# Motorboard.net
KiCad netlist of a schematic drawn in EAGLE
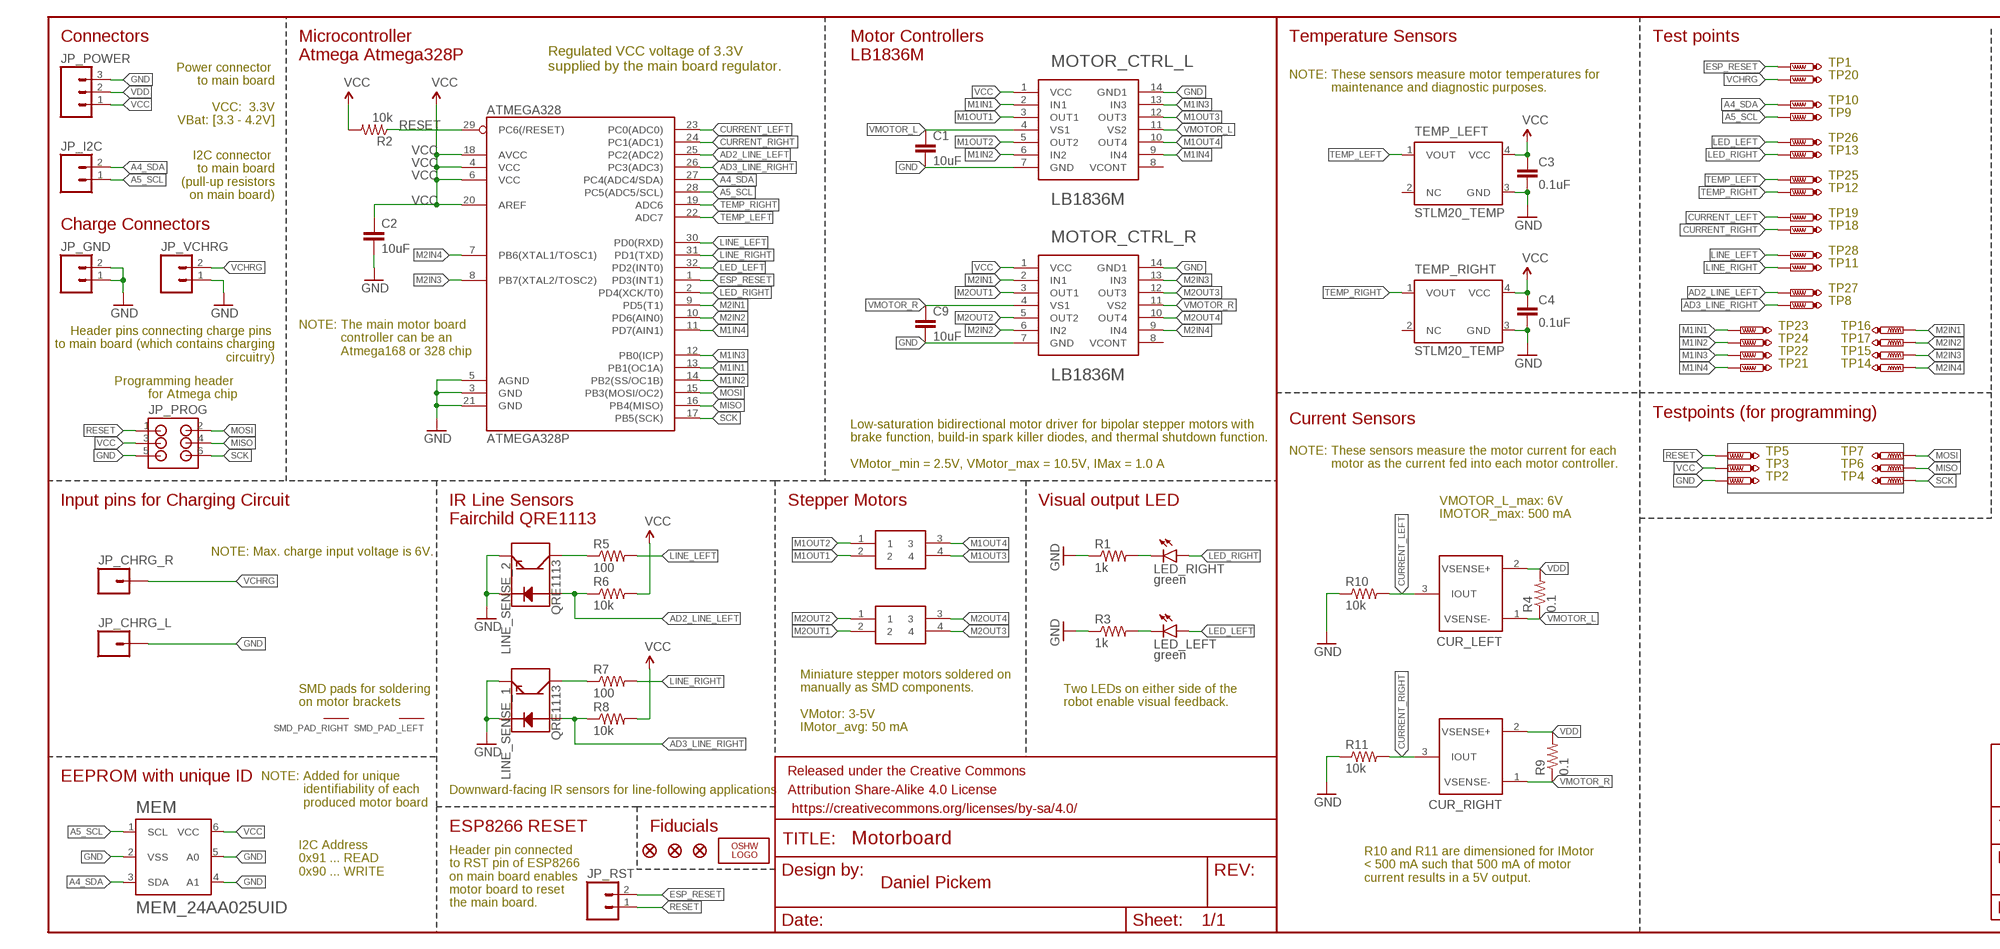
[diagram p0: schematic, sheet 1, part 1 of 2]
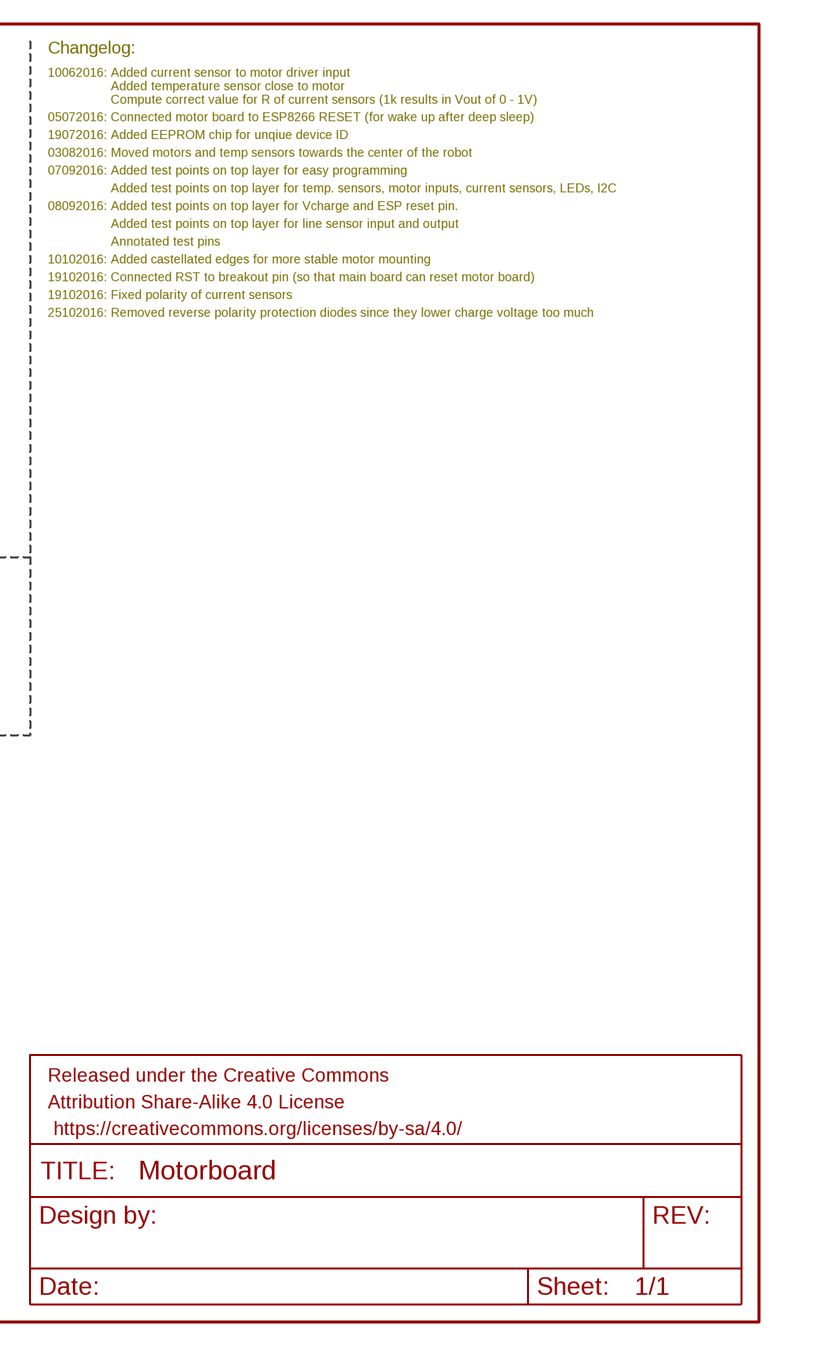
[diagram p1: schematic, sheet 1, part 2 of 2]

(export (version "E")
  (design (tool "Eeschema 10.0.6"))
  (components
    (comp (ref "ATMEGA328P")
      (value "ATMEGA328")
      (footprint "eagle-import:TQFP32-08")
      (libsource (lib "eagle-import") (part "ATMEGA168"))
    )
    (comp (ref "C1")
      (value "10uF")
      (footprint "eagle-import:0805")
      (libsource (lib "eagle-import") (part "2.2UF-25V-+80/-20(0805)"))
    )
    (comp (ref "C2")
      (value "10uF")
      (footprint "eagle-import:0805")
      (libsource (lib "eagle-import") (part "2.2UF-25V-+80/-20(0805)"))
    )
    (comp (ref "C3")
      (value "0.1uF")
      (footprint "eagle-import:0603-CAP")
      (libsource (lib "eagle-import") (part "4.7UF-6.3V-10%(0603)0603"))
    )
    (comp (ref "C4")
      (value "0.1uF")
      (footprint "eagle-import:0603-CAP")
      (libsource (lib "eagle-import") (part "4.7UF-6.3V-10%(0603)0603"))
    )
    (comp (ref "C9")
      (value "10uF")
      (footprint "eagle-import:0805")
      (libsource (lib "eagle-import") (part "2.2UF-25V-+80/-20(0805)"))
    )
    (comp (ref "CUR_LEFT")
      (value "ZXCT1009_CURRENT")
      (footprint "eagle-import:SOT23-3")
      (libsource (lib "eagle-import") (part "ZXCT1009_CURRENT"))
    )
    (comp (ref "CUR_RIGHT")
      (value "ZXCT1009_CURRENT")
      (footprint "eagle-import:SOT23-3")
      (libsource (lib "eagle-import") (part "ZXCT1009_CURRENT"))
    )
    (comp (ref "FRAME1")
      (value "FRAME-LETTER")
      (footprint "eagle-import:CREATIVE_COMMONS")
      (libsource (lib "eagle-import") (part "FRAME-LETTER"))
    )
    (comp (ref "FRAME2")
      (value "FRAME-LETTER")
      (footprint "eagle-import:CREATIVE_COMMONS")
      (libsource (lib "eagle-import") (part "FRAME-LETTER"))
    )
    (comp (ref "JP3")
      (value "FIDUCIAL1X2.5")
      (footprint "eagle-import:FIDUCIAL-1X2.5")
      (libsource (lib "eagle-import") (part "FIDUCIAL1X2.5"))
    )
    (comp (ref "JP4")
      (value "FIDUCIAL1X2.5")
      (footprint "eagle-import:FIDUCIAL-1X2.5")
      (libsource (lib "eagle-import") (part "FIDUCIAL1X2.5"))
    )
    (comp (ref "JP5")
      (value "FIDUCIAL1X2.5")
      (footprint "eagle-import:FIDUCIAL-1X2.5")
      (libsource (lib "eagle-import") (part "FIDUCIAL1X2.5"))
    )
    (comp (ref "JP_CHRG_L")
      (value "M01NOSILK-KIT")
      (footprint "eagle-import:1X01NS-KIT")
      (libsource (lib "eagle-import") (part "M01NOSILK-KIT"))
    )
    (comp (ref "JP_CHRG_R")
      (value "M01NOSILK-KIT")
      (footprint "eagle-import:1X01NS-KIT")
      (libsource (lib "eagle-import") (part "M01NOSILK-KIT"))
    )
    (comp (ref "JP_GND")
      (value "M021X02_NO_SILK")
      (footprint "eagle-import:1X02_NO_SILK")
      (libsource (lib "eagle-import") (part "M021X02_NO_SILK"))
    )
    (comp (ref "JP_I2C")
      (value "M02PTH")
      (footprint "eagle-import:1X02")
      (libsource (lib "eagle-import") (part "M02PTH"))
    )
    (comp (ref "JP_POWER")
      (value "supply")
      (footprint "eagle-import:1X03")
      (libsource (lib "eagle-import") (part "M03PTH"))
    )
    (comp (ref "JP_PROG")
      (value "3X2_SMD_HEADER")
      (footprint "eagle-import:3X2_SMD_HEADER")
      (libsource (lib "eagle-import") (part "3X2_SMD_HEADER"))
    )
    (comp (ref "JP_RST")
      (value "M021X02_NO_SILK")
      (footprint "eagle-import:1X02_NO_SILK")
      (libsource (lib "eagle-import") (part "M021X02_NO_SILK"))
    )
    (comp (ref "JP_VCHRG")
      (value "M021X02_NO_SILK")
      (footprint "eagle-import:1X02_NO_SILK")
      (libsource (lib "eagle-import") (part "M021X02_NO_SILK"))
    )
    (comp (ref "LED_LEFT")
      (value "green")
      (footprint "eagle-import:LED-0603")
      (libsource (lib "eagle-import") (part "LED0603"))
    )
    (comp (ref "LED_RIGHT")
      (value "green")
      (footprint "eagle-import:LED-0603")
      (libsource (lib "eagle-import") (part "LED0603"))
    )
    (comp (ref "LINE_SENSE_1")
      (value "QRE1113")
      (footprint "eagle-import:QRE1113")
      (libsource (lib "eagle-import") (part "QRE1113"))
    )
    (comp (ref "LINE_SENSE_2")
      (value "QRE1113")
      (footprint "eagle-import:QRE1113")
      (libsource (lib "eagle-import") (part "QRE1113"))
    )
    (comp (ref "LOGO1")
      (value "OSHW_LOGO_FILLX0100-NT")
      (footprint "eagle-import:OSHW_FILLX100_NOTEXT")
      (libsource (lib "eagle-import") (part "OSHW_LOGO_FILLX0100-NT"))
    )
    (comp (ref "M1")
      (value "STEPPER_MOTOR_SMD")
      (footprint "eagle-import:STEPPER_MOTOR_SMD")
      (libsource (lib "eagle-import") (part "STEPPER_MOTOR_SMD"))
    )
    (comp (ref "M2")
      (value "STEPPER_MOTOR_SMD")
      (footprint "eagle-import:STEPPER_MOTOR_SMD")
      (libsource (lib "eagle-import") (part "STEPPER_MOTOR_SMD"))
    )
    (comp (ref "MEM")
      (value "MEM_24AA025UID")
      (footprint "eagle-import:SOT23-6-MCP1640")
      (libsource (lib "eagle-import") (part "MEM_24AA025UID"))
    )
    (comp (ref "MOTOR_CTRL_L")
      (value "LB1836M")
      (footprint "eagle-import:LSOP-14")
      (libsource (lib "eagle-import") (part "LB1836M"))
    )
    (comp (ref "MOTOR_CTRL_R")
      (value "LB1836M")
      (footprint "eagle-import:LSOP-14")
      (libsource (lib "eagle-import") (part "LB1836M"))
    )
    (comp (ref "R1")
      (value "1k")
      (footprint "eagle-import:0603")
      (libsource (lib "eagle-import") (part "1.5KOHM1/10W1%(0603)"))
    )
    (comp (ref "R2")
      (value "10k")
      (footprint "eagle-import:0603")
      (libsource (lib "eagle-import") (part "1.5KOHM1/10W1%(0603)"))
    )
    (comp (ref "R3")
      (value "1k")
      (footprint "eagle-import:0603")
      (libsource (lib "eagle-import") (part "1.5KOHM1/10W1%(0603)"))
    )
    (comp (ref "R4")
      (value "0.1")
      (footprint "eagle-import:1206")
      (libsource (lib "eagle-import") (part "RESISTOR1206"))
    )
    (comp (ref "R5")
      (value "100")
      (footprint "eagle-import:0603")
      (libsource (lib "eagle-import") (part "1.5KOHM1/10W1%(0603)"))
    )
    (comp (ref "R6")
      (value "10k")
      (footprint "eagle-import:0603")
      (libsource (lib "eagle-import") (part "1.5KOHM1/10W1%(0603)"))
    )
    (comp (ref "R7")
      (value "100")
      (footprint "eagle-import:0603")
      (libsource (lib "eagle-import") (part "1.5KOHM1/10W1%(0603)"))
    )
    (comp (ref "R8")
      (value "10k")
      (footprint "eagle-import:0603")
      (libsource (lib "eagle-import") (part "1.5KOHM1/10W1%(0603)"))
    )
    (comp (ref "R9")
      (value "0.1")
      (footprint "eagle-import:1206")
      (libsource (lib "eagle-import") (part "RESISTOR1206"))
    )
    (comp (ref "R10")
      (value "10k")
      (footprint "eagle-import:0603")
      (libsource (lib "eagle-import") (part "1.5KOHM1/10W1%(0603)"))
    )
    (comp (ref "R11")
      (value "10k")
      (footprint "eagle-import:0603")
      (libsource (lib "eagle-import") (part "1.5KOHM1/10W1%(0603)"))
    )
    (comp (ref "SMD_PAD_LEFT")
      (value "PIN_SMD2.5X1.0")
      (footprint "eagle-import:PIN_SMD_2.5X1.0")
      (libsource (lib "eagle-import") (part "PIN_SMD2.5X1.0"))
    )
    (comp (ref "SMD_PAD_RIGHT")
      (value "PIN_SMD2.5X1.0")
      (footprint "eagle-import:PIN_SMD_2.5X1.0")
      (libsource (lib "eagle-import") (part "PIN_SMD2.5X1.0"))
    )
    (comp (ref "TEMP_LEFT")
      (value "STLM20_TEMP")
      (footprint "eagle-import:UDFN4")
      (libsource (lib "eagle-import") (part "STLM20_TEMP"))
    )
    (comp (ref "TEMP_RIGHT")
      (value "STLM20_TEMP")
      (footprint "eagle-import:UDFN4")
      (libsource (lib "eagle-import") (part "STLM20_TEMP"))
    )
    (comp (ref "TP1")
      (value "PTR1B1,27")
      (footprint "eagle-import:B1,27")
      (libsource (lib "eagle-import") (part "PTR1B1,27"))
    )
    (comp (ref "TP2")
      (value "PTR1B1,27")
      (footprint "eagle-import:B1,27")
      (libsource (lib "eagle-import") (part "PTR1B1,27"))
    )
    (comp (ref "TP3")
      (value "PTR1B1,27")
      (footprint "eagle-import:B1,27")
      (libsource (lib "eagle-import") (part "PTR1B1,27"))
    )
    (comp (ref "TP4")
      (value "PTR1B1,27")
      (footprint "eagle-import:B1,27")
      (libsource (lib "eagle-import") (part "PTR1B1,27"))
    )
    (comp (ref "TP5")
      (value "PTR1B1,27")
      (footprint "eagle-import:B1,27")
      (libsource (lib "eagle-import") (part "PTR1B1,27"))
    )
    (comp (ref "TP6")
      (value "PTR1B1,27")
      (footprint "eagle-import:B1,27")
      (libsource (lib "eagle-import") (part "PTR1B1,27"))
    )
    (comp (ref "TP7")
      (value "PTR1B1,27")
      (footprint "eagle-import:B1,27")
      (libsource (lib "eagle-import") (part "PTR1B1,27"))
    )
    (comp (ref "TP8")
      (value "PTR1B1,27")
      (footprint "eagle-import:B1,27")
      (libsource (lib "eagle-import") (part "PTR1B1,27"))
    )
    (comp (ref "TP9")
      (value "PTR1B1,27")
      (footprint "eagle-import:B1,27")
      (libsource (lib "eagle-import") (part "PTR1B1,27"))
    )
    (comp (ref "TP10")
      (value "PTR1B1,27")
      (footprint "eagle-import:B1,27")
      (libsource (lib "eagle-import") (part "PTR1B1,27"))
    )
    (comp (ref "TP11")
      (value "PTR1B1,27")
      (footprint "eagle-import:B1,27")
      (libsource (lib "eagle-import") (part "PTR1B1,27"))
    )
    (comp (ref "TP12")
      (value "PTR1B1,27")
      (footprint "eagle-import:B1,27")
      (libsource (lib "eagle-import") (part "PTR1B1,27"))
    )
    (comp (ref "TP13")
      (value "PTR1B1,27")
      (footprint "eagle-import:B1,27")
      (libsource (lib "eagle-import") (part "PTR1B1,27"))
    )
    (comp (ref "TP14")
      (value "PTR1B1,27")
      (footprint "eagle-import:B1,27")
      (libsource (lib "eagle-import") (part "PTR1B1,27"))
    )
    (comp (ref "TP15")
      (value "PTR1B1,27")
      (footprint "eagle-import:B1,27")
      (libsource (lib "eagle-import") (part "PTR1B1,27"))
    )
    (comp (ref "TP16")
      (value "PTR1B1,27")
      (footprint "eagle-import:B1,27")
      (libsource (lib "eagle-import") (part "PTR1B1,27"))
    )
    (comp (ref "TP17")
      (value "PTR1B1,27")
      (footprint "eagle-import:B1,27")
      (libsource (lib "eagle-import") (part "PTR1B1,27"))
    )
    (comp (ref "TP18")
      (value "PTR1B1,27")
      (footprint "eagle-import:B1,27")
      (libsource (lib "eagle-import") (part "PTR1B1,27"))
    )
    (comp (ref "TP19")
      (value "PTR1B1,27")
      (footprint "eagle-import:B1,27")
      (libsource (lib "eagle-import") (part "PTR1B1,27"))
    )
    (comp (ref "TP20")
      (value "PTR1B1,27")
      (footprint "eagle-import:B1,27")
      (libsource (lib "eagle-import") (part "PTR1B1,27"))
    )
    (comp (ref "TP21")
      (value "PTR1B1,27")
      (footprint "eagle-import:B1,27")
      (libsource (lib "eagle-import") (part "PTR1B1,27"))
    )
    (comp (ref "TP22")
      (value "PTR1B1,27")
      (footprint "eagle-import:B1,27")
      (libsource (lib "eagle-import") (part "PTR1B1,27"))
    )
    (comp (ref "TP23")
      (value "PTR1B1,27")
      (footprint "eagle-import:B1,27")
      (libsource (lib "eagle-import") (part "PTR1B1,27"))
    )
    (comp (ref "TP24")
      (value "PTR1B1,27")
      (footprint "eagle-import:B1,27")
      (libsource (lib "eagle-import") (part "PTR1B1,27"))
    )
    (comp (ref "TP25")
      (value "PTR1B1,27")
      (footprint "eagle-import:B1,27")
      (libsource (lib "eagle-import") (part "PTR1B1,27"))
    )
    (comp (ref "TP26")
      (value "PTR1B1,27")
      (footprint "eagle-import:B1,27")
      (libsource (lib "eagle-import") (part "PTR1B1,27"))
    )
    (comp (ref "TP27")
      (value "PTR1B1,27")
      (footprint "eagle-import:B1,27")
      (libsource (lib "eagle-import") (part "PTR1B1,27"))
    )
    (comp (ref "TP28")
      (value "PTR1B1,27")
      (footprint "eagle-import:B1,27")
      (libsource (lib "eagle-import") (part "PTR1B1,27"))
    )
  )
  (nets
    (net (code "1") (name "A4_SDA") (class "Default")
      (node (ref "ATMEGA328P") (pin "27") (pinfunction "PC4(ADC4/SDA)_27") (pintype "bidirectional"))
      (node (ref "JP_I2C") (pin "2") (pinfunction "2_2") (pintype "passive"))
      (node (ref "MEM") (pin "3") (pinfunction "SDA_3") (pintype "bidirectional"))
      (node (ref "TP10") (pin "TP") (pinfunction "TP_TP") (pintype "input"))
    )
    (net (code "2") (name "A5_SCL") (class "Default")
      (node (ref "ATMEGA328P") (pin "28") (pinfunction "PC5(ADC5/SCL)_28") (pintype "bidirectional"))
      (node (ref "JP_I2C") (pin "1") (pinfunction "1_1") (pintype "passive"))
      (node (ref "MEM") (pin "1") (pinfunction "SCL_1") (pintype "bidirectional"))
      (node (ref "TP9") (pin "TP") (pinfunction "TP_TP") (pintype "input"))
    )
    (net (code "3") (name "AD2_LINE_LEFT") (class "Default")
      (node (ref "ATMEGA328P") (pin "25") (pinfunction "PC2(ADC2)_25") (pintype "bidirectional"))
      (node (ref "LINE_SENSE_2") (pin "1") (pinfunction "A_1") (pintype "bidirectional"))
      (node (ref "R6") (pin "1") (pinfunction "1_1") (pintype "passive"))
      (node (ref "TP27") (pin "TP") (pinfunction "TP_TP") (pintype "input"))
    )
    (net (code "4") (name "AD3_LINE_RIGHT") (class "Default")
      (node (ref "ATMEGA328P") (pin "26") (pinfunction "PC3(ADC3)_26") (pintype "bidirectional"))
      (node (ref "LINE_SENSE_1") (pin "1") (pinfunction "A_1") (pintype "bidirectional"))
      (node (ref "R8") (pin "1") (pinfunction "1_1") (pintype "passive"))
      (node (ref "TP8") (pin "TP") (pinfunction "TP_TP") (pintype "input"))
    )
    (net (code "5") (name "CURRENT_LEFT") (class "Default")
      (node (ref "ATMEGA328P") (pin "23") (pinfunction "PC0(ADC0)_23") (pintype "bidirectional"))
      (node (ref "CUR_LEFT") (pin "3") (pinfunction "IOUT_3") (pintype "bidirectional"))
      (node (ref "R10") (pin "2") (pinfunction "2_2") (pintype "passive"))
      (node (ref "TP19") (pin "TP") (pinfunction "TP_TP") (pintype "input"))
    )
    (net (code "6") (name "CURRENT_RIGHT") (class "Default")
      (node (ref "ATMEGA328P") (pin "24") (pinfunction "PC1(ADC1)_24") (pintype "bidirectional"))
      (node (ref "CUR_RIGHT") (pin "3") (pinfunction "IOUT_3") (pintype "bidirectional"))
      (node (ref "R11") (pin "2") (pinfunction "2_2") (pintype "passive"))
      (node (ref "TP18") (pin "TP") (pinfunction "TP_TP") (pintype "input"))
    )
    (net (code "7") (name "ESP_RESET") (class "Default")
      (node (ref "ATMEGA328P") (pin "1") (pinfunction "PD3(INT1)_1") (pintype "bidirectional"))
      (node (ref "JP_RST") (pin "2") (pinfunction "2_2") (pintype "passive"))
      (node (ref "TP1") (pin "TP") (pinfunction "TP_TP") (pintype "input"))
    )
    (net (code "8") (name "GND") (class "Default")
      (node (ref "ATMEGA328P") (pin "21") (pinfunction "GND_21") (pintype "bidirectional"))
      (node (ref "ATMEGA328P") (pin "3") (pinfunction "GND_3") (pintype "bidirectional"))
      (node (ref "ATMEGA328P") (pin "5") (pinfunction "AGND_5") (pintype "bidirectional"))
      (node (ref "C1") (pin "2") (pinfunction "2_2") (pintype "passive"))
      (node (ref "C2") (pin "2") (pinfunction "2_2") (pintype "passive"))
      (node (ref "C3") (pin "2") (pinfunction "2_2") (pintype "passive"))
      (node (ref "C4") (pin "1") (pinfunction "1_1") (pintype "passive"))
      (node (ref "C9") (pin "2") (pinfunction "2_2") (pintype "passive"))
      (node (ref "JP_CHRG_L") (pin "1") (pinfunction "1_1") (pintype "passive"))
      (node (ref "JP_GND") (pin "1") (pinfunction "1_1") (pintype "passive"))
      (node (ref "JP_GND") (pin "2") (pinfunction "2_2") (pintype "passive"))
      (node (ref "JP_POWER") (pin "3") (pinfunction "3_3") (pintype "passive"))
      (node (ref "JP_PROG") (pin "5") (pinfunction "5_5") (pintype "bidirectional"))
      (node (ref "JP_VCHRG") (pin "1") (pinfunction "1_1") (pintype "passive"))
      (node (ref "LINE_SENSE_1") (pin "2") (pinfunction "K_2") (pintype "bidirectional"))
      (node (ref "LINE_SENSE_1") (pin "4") (pinfunction "E_4") (pintype "bidirectional"))
      (node (ref "LINE_SENSE_2") (pin "2") (pinfunction "K_2") (pintype "bidirectional"))
      (node (ref "LINE_SENSE_2") (pin "4") (pinfunction "E_4") (pintype "bidirectional"))
      (node (ref "MEM") (pin "2") (pinfunction "VSS_2") (pintype "bidirectional"))
      (node (ref "MEM") (pin "4") (pinfunction "A1_4") (pintype "bidirectional"))
      (node (ref "MEM") (pin "5") (pinfunction "A0_5") (pintype "bidirectional"))
      (node (ref "MOTOR_CTRL_L") (pin "14") (pinfunction "GND1_14") (pintype "bidirectional"))
      (node (ref "MOTOR_CTRL_L") (pin "7") (pinfunction "GND_7") (pintype "bidirectional"))
      (node (ref "MOTOR_CTRL_R") (pin "14") (pinfunction "GND1_14") (pintype "bidirectional"))
      (node (ref "MOTOR_CTRL_R") (pin "7") (pinfunction "GND_7") (pintype "bidirectional"))
      (node (ref "R1") (pin "1") (pinfunction "1_1") (pintype "passive"))
      (node (ref "R10") (pin "1") (pinfunction "1_1") (pintype "passive"))
      (node (ref "R11") (pin "1") (pinfunction "1_1") (pintype "passive"))
      (node (ref "R3") (pin "1") (pinfunction "1_1") (pintype "passive"))
      (node (ref "TEMP_LEFT") (pin "3") (pinfunction "GND_3") (pintype "bidirectional"))
      (node (ref "TEMP_RIGHT") (pin "3") (pinfunction "GND_3") (pintype "bidirectional"))
      (node (ref "TP2") (pin "TP") (pinfunction "TP_TP") (pintype "input"))
    )
    (net (code "9") (name "LED_LEFT") (class "Default")
      (node (ref "ATMEGA328P") (pin "32") (pinfunction "PD2(INT0)_32") (pintype "bidirectional"))
      (node (ref "LED_LEFT") (pin "A") (pinfunction "A_A") (pintype "passive"))
      (node (ref "TP26") (pin "TP") (pinfunction "TP_TP") (pintype "input"))
    )
    (net (code "10") (name "LED_RIGHT") (class "Default")
      (node (ref "ATMEGA328P") (pin "2") (pinfunction "PD4(XCK/T0)_2") (pintype "bidirectional"))
      (node (ref "LED_RIGHT") (pin "A") (pinfunction "A_A") (pintype "passive"))
      (node (ref "TP13") (pin "TP") (pinfunction "TP_TP") (pintype "input"))
    )
    (net (code "11") (name "LINE_LEFT") (class "Default")
      (node (ref "ATMEGA328P") (pin "30") (pinfunction "PD0(RXD)_30") (pintype "bidirectional"))
      (node (ref "R5") (pin "2") (pinfunction "2_2") (pintype "passive"))
      (node (ref "TP28") (pin "TP") (pinfunction "TP_TP") (pintype "input"))
    )
    (net (code "12") (name "LINE_RIGHT") (class "Default")
      (node (ref "ATMEGA328P") (pin "31") (pinfunction "PD1(TXD)_31") (pintype "bidirectional"))
      (node (ref "R7") (pin "2") (pinfunction "2_2") (pintype "passive"))
      (node (ref "TP11") (pin "TP") (pinfunction "TP_TP") (pintype "input"))
    )
    (net (code "13") (name "M1IN1") (class "Default")
      (node (ref "ATMEGA328P") (pin "13") (pinfunction "PB1(OC1A)_13") (pintype "bidirectional"))
      (node (ref "MOTOR_CTRL_L") (pin "2") (pinfunction "IN1_2") (pintype "bidirectional"))
      (node (ref "TP23") (pin "TP") (pinfunction "TP_TP") (pintype "input"))
    )
    (net (code "14") (name "M1IN2") (class "Default")
      (node (ref "ATMEGA328P") (pin "14") (pinfunction "PB2(SS/OC1B)_14") (pintype "bidirectional"))
      (node (ref "MOTOR_CTRL_L") (pin "6") (pinfunction "IN2_6") (pintype "bidirectional"))
      (node (ref "TP24") (pin "TP") (pinfunction "TP_TP") (pintype "input"))
    )
    (net (code "15") (name "M1IN3") (class "Default")
      (node (ref "ATMEGA328P") (pin "12") (pinfunction "PB0(ICP)_12") (pintype "bidirectional"))
      (node (ref "MOTOR_CTRL_L") (pin "13") (pinfunction "IN3_13") (pintype "bidirectional"))
      (node (ref "TP22") (pin "TP") (pinfunction "TP_TP") (pintype "input"))
    )
    (net (code "16") (name "M1IN4") (class "Default")
      (node (ref "ATMEGA328P") (pin "11") (pinfunction "PD7(AIN1)_11") (pintype "bidirectional"))
      (node (ref "MOTOR_CTRL_L") (pin "9") (pinfunction "IN4_9") (pintype "bidirectional"))
      (node (ref "TP21") (pin "TP") (pinfunction "TP_TP") (pintype "input"))
    )
    (net (code "17") (name "M1OUT1") (class "Default")
      (node (ref "M1") (pin "2") (pinfunction "2_2") (pintype "bidirectional"))
      (node (ref "MOTOR_CTRL_L") (pin "3") (pinfunction "OUT1_3") (pintype "bidirectional"))
    )
    (net (code "18") (name "M1OUT2") (class "Default")
      (node (ref "M1") (pin "1") (pinfunction "1_1") (pintype "bidirectional"))
      (node (ref "MOTOR_CTRL_L") (pin "5") (pinfunction "OUT2_5") (pintype "bidirectional"))
    )
    (net (code "19") (name "M1OUT3") (class "Default")
      (node (ref "M1") (pin "4") (pinfunction "4_4") (pintype "bidirectional"))
      (node (ref "MOTOR_CTRL_L") (pin "12") (pinfunction "OUT3_12") (pintype "bidirectional"))
    )
    (net (code "20") (name "M1OUT4") (class "Default")
      (node (ref "M1") (pin "3") (pinfunction "3_3") (pintype "bidirectional"))
      (node (ref "MOTOR_CTRL_L") (pin "10") (pinfunction "OUT4_10") (pintype "bidirectional"))
    )
    (net (code "21") (name "M2IN1") (class "Default")
      (node (ref "ATMEGA328P") (pin "9") (pinfunction "PD5(T1)_9") (pintype "bidirectional"))
      (node (ref "MOTOR_CTRL_R") (pin "2") (pinfunction "IN1_2") (pintype "bidirectional"))
      (node (ref "TP16") (pin "TP") (pinfunction "TP_TP") (pintype "input"))
    )
    (net (code "22") (name "M2IN2") (class "Default")
      (node (ref "ATMEGA328P") (pin "10") (pinfunction "PD6(AIN0)_10") (pintype "bidirectional"))
      (node (ref "MOTOR_CTRL_R") (pin "6") (pinfunction "IN2_6") (pintype "bidirectional"))
      (node (ref "TP17") (pin "TP") (pinfunction "TP_TP") (pintype "input"))
    )
    (net (code "23") (name "M2IN3") (class "Default")
      (node (ref "ATMEGA328P") (pin "8") (pinfunction "PB7(XTAL2/TOSC2)_8") (pintype "bidirectional"))
      (node (ref "MOTOR_CTRL_R") (pin "13") (pinfunction "IN3_13") (pintype "bidirectional"))
      (node (ref "TP15") (pin "TP") (pinfunction "TP_TP") (pintype "input"))
    )
    (net (code "24") (name "M2IN4") (class "Default")
      (node (ref "ATMEGA328P") (pin "7") (pinfunction "PB6(XTAL1/TOSC1)_7") (pintype "bidirectional"))
      (node (ref "MOTOR_CTRL_R") (pin "9") (pinfunction "IN4_9") (pintype "bidirectional"))
      (node (ref "TP14") (pin "TP") (pinfunction "TP_TP") (pintype "input"))
    )
    (net (code "25") (name "M2OUT1") (class "Default")
      (node (ref "M2") (pin "2") (pinfunction "2_2") (pintype "bidirectional"))
      (node (ref "MOTOR_CTRL_R") (pin "3") (pinfunction "OUT1_3") (pintype "bidirectional"))
    )
    (net (code "26") (name "M2OUT2") (class "Default")
      (node (ref "M2") (pin "1") (pinfunction "1_1") (pintype "bidirectional"))
      (node (ref "MOTOR_CTRL_R") (pin "5") (pinfunction "OUT2_5") (pintype "bidirectional"))
    )
    (net (code "27") (name "M2OUT3") (class "Default")
      (node (ref "M2") (pin "4") (pinfunction "4_4") (pintype "bidirectional"))
      (node (ref "MOTOR_CTRL_R") (pin "12") (pinfunction "OUT3_12") (pintype "bidirectional"))
    )
    (net (code "28") (name "M2OUT4") (class "Default")
      (node (ref "M2") (pin "3") (pinfunction "3_3") (pintype "bidirectional"))
      (node (ref "MOTOR_CTRL_R") (pin "10") (pinfunction "OUT4_10") (pintype "bidirectional"))
    )
    (net (code "29") (name "MISO") (class "Default")
      (node (ref "ATMEGA328P") (pin "16") (pinfunction "PB4(MISO)_16") (pintype "bidirectional"))
      (node (ref "JP_PROG") (pin "4") (pinfunction "4_4") (pintype "bidirectional"))
      (node (ref "TP6") (pin "TP") (pinfunction "TP_TP") (pintype "input"))
    )
    (net (code "30") (name "MOSI") (class "Default")
      (node (ref "ATMEGA328P") (pin "15") (pinfunction "PB3(MOSI/OC2)_15") (pintype "bidirectional"))
      (node (ref "JP_PROG") (pin "2") (pinfunction "2_2") (pintype "bidirectional"))
      (node (ref "TP7") (pin "TP") (pinfunction "TP_TP") (pintype "input"))
    )
    (net (code "31") (name "Net-(LED_LEFT-PadC)") (class "Default")
      (node (ref "LED_LEFT") (pin "C") (pinfunction "C_C") (pintype "passive"))
      (node (ref "R3") (pin "2") (pinfunction "2_2") (pintype "passive"))
    )
    (net (code "32") (name "Net-(LED_RIGHT-PadC)") (class "Default")
      (node (ref "LED_RIGHT") (pin "C") (pinfunction "C_C") (pintype "passive"))
      (node (ref "R1") (pin "2") (pinfunction "2_2") (pintype "passive"))
    )
    (net (code "33") (name "Net-(LINE_SENSE_1-C)") (class "Default")
      (node (ref "LINE_SENSE_1") (pin "3") (pinfunction "C_3") (pintype "bidirectional"))
      (node (ref "R7") (pin "1") (pinfunction "1_1") (pintype "passive"))
    )
    (net (code "34") (name "Net-(LINE_SENSE_2-C)") (class "Default")
      (node (ref "LINE_SENSE_2") (pin "3") (pinfunction "C_3") (pintype "bidirectional"))
      (node (ref "R5") (pin "1") (pinfunction "1_1") (pintype "passive"))
    )
    (net (code "35") (name "RESET") (class "Default")
      (node (ref "ATMEGA328P") (pin "29") (pinfunction "PC6(/RESET)_29") (pintype "bidirectional"))
      (node (ref "JP_PROG") (pin "1") (pinfunction "1_1") (pintype "bidirectional"))
      (node (ref "JP_RST") (pin "1") (pinfunction "1_1") (pintype "passive"))
      (node (ref "R2") (pin "1") (pinfunction "1_1") (pintype "passive"))
      (node (ref "TP5") (pin "TP") (pinfunction "TP_TP") (pintype "input"))
    )
    (net (code "36") (name "SCK") (class "Default")
      (node (ref "ATMEGA328P") (pin "17") (pinfunction "PB5(SCK)_17") (pintype "bidirectional"))
      (node (ref "JP_PROG") (pin "6") (pinfunction "6_6") (pintype "bidirectional"))
      (node (ref "TP4") (pin "TP") (pinfunction "TP_TP") (pintype "input"))
    )
    (net (code "37") (name "TEMP_LEFT") (class "Default")
      (node (ref "ATMEGA328P") (pin "22") (pinfunction "ADC7_22") (pintype "bidirectional"))
      (node (ref "TEMP_LEFT") (pin "1") (pinfunction "VOUT_1") (pintype "bidirectional"))
      (node (ref "TP25") (pin "TP") (pinfunction "TP_TP") (pintype "input"))
    )
    (net (code "38") (name "TEMP_RIGHT") (class "Default")
      (node (ref "ATMEGA328P") (pin "19") (pinfunction "ADC6_19") (pintype "bidirectional"))
      (node (ref "TEMP_RIGHT") (pin "1") (pinfunction "VOUT_1") (pintype "bidirectional"))
      (node (ref "TP12") (pin "TP") (pinfunction "TP_TP") (pintype "input"))
    )
    (net (code "39") (name "VCC") (class "Default")
      (node (ref "ATMEGA328P") (pin "18") (pinfunction "AVCC_18") (pintype "bidirectional"))
      (node (ref "ATMEGA328P") (pin "20") (pinfunction "AREF_20") (pintype "bidirectional"))
      (node (ref "ATMEGA328P") (pin "4") (pinfunction "VCC_4") (pintype "bidirectional"))
      (node (ref "ATMEGA328P") (pin "6") (pinfunction "VCC_6") (pintype "bidirectional"))
      (node (ref "C2") (pin "1") (pinfunction "1_1") (pintype "passive"))
      (node (ref "C3") (pin "1") (pinfunction "1_1") (pintype "passive"))
      (node (ref "C4") (pin "2") (pinfunction "2_2") (pintype "passive"))
      (node (ref "JP_POWER") (pin "1") (pinfunction "1_1") (pintype "passive"))
      (node (ref "JP_PROG") (pin "3") (pinfunction "3_3") (pintype "bidirectional"))
      (node (ref "MEM") (pin "6") (pinfunction "VCC_6") (pintype "bidirectional"))
      (node (ref "MOTOR_CTRL_L") (pin "1") (pinfunction "VCC_1") (pintype "bidirectional"))
      (node (ref "MOTOR_CTRL_R") (pin "1") (pinfunction "VCC_1") (pintype "bidirectional"))
      (node (ref "R2") (pin "2") (pinfunction "2_2") (pintype "passive"))
      (node (ref "R6") (pin "2") (pinfunction "2_2") (pintype "passive"))
      (node (ref "R8") (pin "2") (pinfunction "2_2") (pintype "passive"))
      (node (ref "TEMP_LEFT") (pin "4") (pinfunction "VCC_4") (pintype "bidirectional"))
      (node (ref "TEMP_RIGHT") (pin "4") (pinfunction "VCC_4") (pintype "bidirectional"))
      (node (ref "TP3") (pin "TP") (pinfunction "TP_TP") (pintype "input"))
    )
    (net (code "40") (name "VCHRG") (class "Default")
      (node (ref "JP_CHRG_R") (pin "1") (pinfunction "1_1") (pintype "passive"))
      (node (ref "JP_VCHRG") (pin "2") (pinfunction "2_2") (pintype "passive"))
      (node (ref "TP20") (pin "TP") (pinfunction "TP_TP") (pintype "input"))
    )
    (net (code "41") (name "VDD") (class "Default")
      (node (ref "CUR_LEFT") (pin "2") (pinfunction "VSENSE+_2") (pintype "bidirectional"))
      (node (ref "CUR_RIGHT") (pin "2") (pinfunction "VSENSE+_2") (pintype "bidirectional"))
      (node (ref "JP_POWER") (pin "2") (pinfunction "2_2") (pintype "passive"))
      (node (ref "R4") (pin "2") (pinfunction "2_2") (pintype "passive"))
      (node (ref "R9") (pin "2") (pinfunction "2_2") (pintype "passive"))
    )
    (net (code "42") (name "VMOTOR_L") (class "Default")
      (node (ref "C1") (pin "1") (pinfunction "1_1") (pintype "passive"))
      (node (ref "CUR_LEFT") (pin "1") (pinfunction "VSENSE-_1") (pintype "bidirectional"))
      (node (ref "MOTOR_CTRL_L") (pin "11") (pinfunction "VS2_11") (pintype "bidirectional"))
      (node (ref "MOTOR_CTRL_L") (pin "4") (pinfunction "VS1_4") (pintype "bidirectional"))
      (node (ref "R4") (pin "1") (pinfunction "1_1") (pintype "passive"))
    )
    (net (code "43") (name "VMOTOR_R") (class "Default")
      (node (ref "C9") (pin "1") (pinfunction "1_1") (pintype "passive"))
      (node (ref "CUR_RIGHT") (pin "1") (pinfunction "VSENSE-_1") (pintype "bidirectional"))
      (node (ref "MOTOR_CTRL_R") (pin "11") (pinfunction "VS2_11") (pintype "bidirectional"))
      (node (ref "MOTOR_CTRL_R") (pin "4") (pinfunction "VS1_4") (pintype "bidirectional"))
      (node (ref "R9") (pin "1") (pinfunction "1_1") (pintype "passive"))
    )
    (net (code "44") (name "unconnected-(MOTOR_CTRL_L-VCONT-Pad8)") (class "Default")
      (node (ref "MOTOR_CTRL_L") (pin "8") (pinfunction "VCONT_8") (pintype "bidirectional"))
    )
    (net (code "45") (name "unconnected-(MOTOR_CTRL_R-VCONT-Pad8)") (class "Default")
      (node (ref "MOTOR_CTRL_R") (pin "8") (pinfunction "VCONT_8") (pintype "bidirectional"))
    )
    (net (code "46") (name "unconnected-(SMD_PAD_LEFT-1-PadP$1)") (class "Default")
      (node (ref "SMD_PAD_LEFT") (pin "P$1") (pinfunction "1_P$1") (pintype "bidirectional"))
    )
    (net (code "47") (name "unconnected-(SMD_PAD_RIGHT-1-PadP$1)") (class "Default")
      (node (ref "SMD_PAD_RIGHT") (pin "P$1") (pinfunction "1_P$1") (pintype "bidirectional"))
    )
    (net (code "48") (name "unconnected-(TEMP_LEFT-NC-Pad2)") (class "Default")
      (node (ref "TEMP_LEFT") (pin "2") (pinfunction "NC_2") (pintype "bidirectional"))
    )
    (net (code "49") (name "unconnected-(TEMP_RIGHT-NC-Pad2)") (class "Default")
      (node (ref "TEMP_RIGHT") (pin "2") (pinfunction "NC_2") (pintype "bidirectional"))
    )
  )
)
